# sofi_v7_main_rev2_1.net
KiCad netlist of a schematic drawn in EAGLE
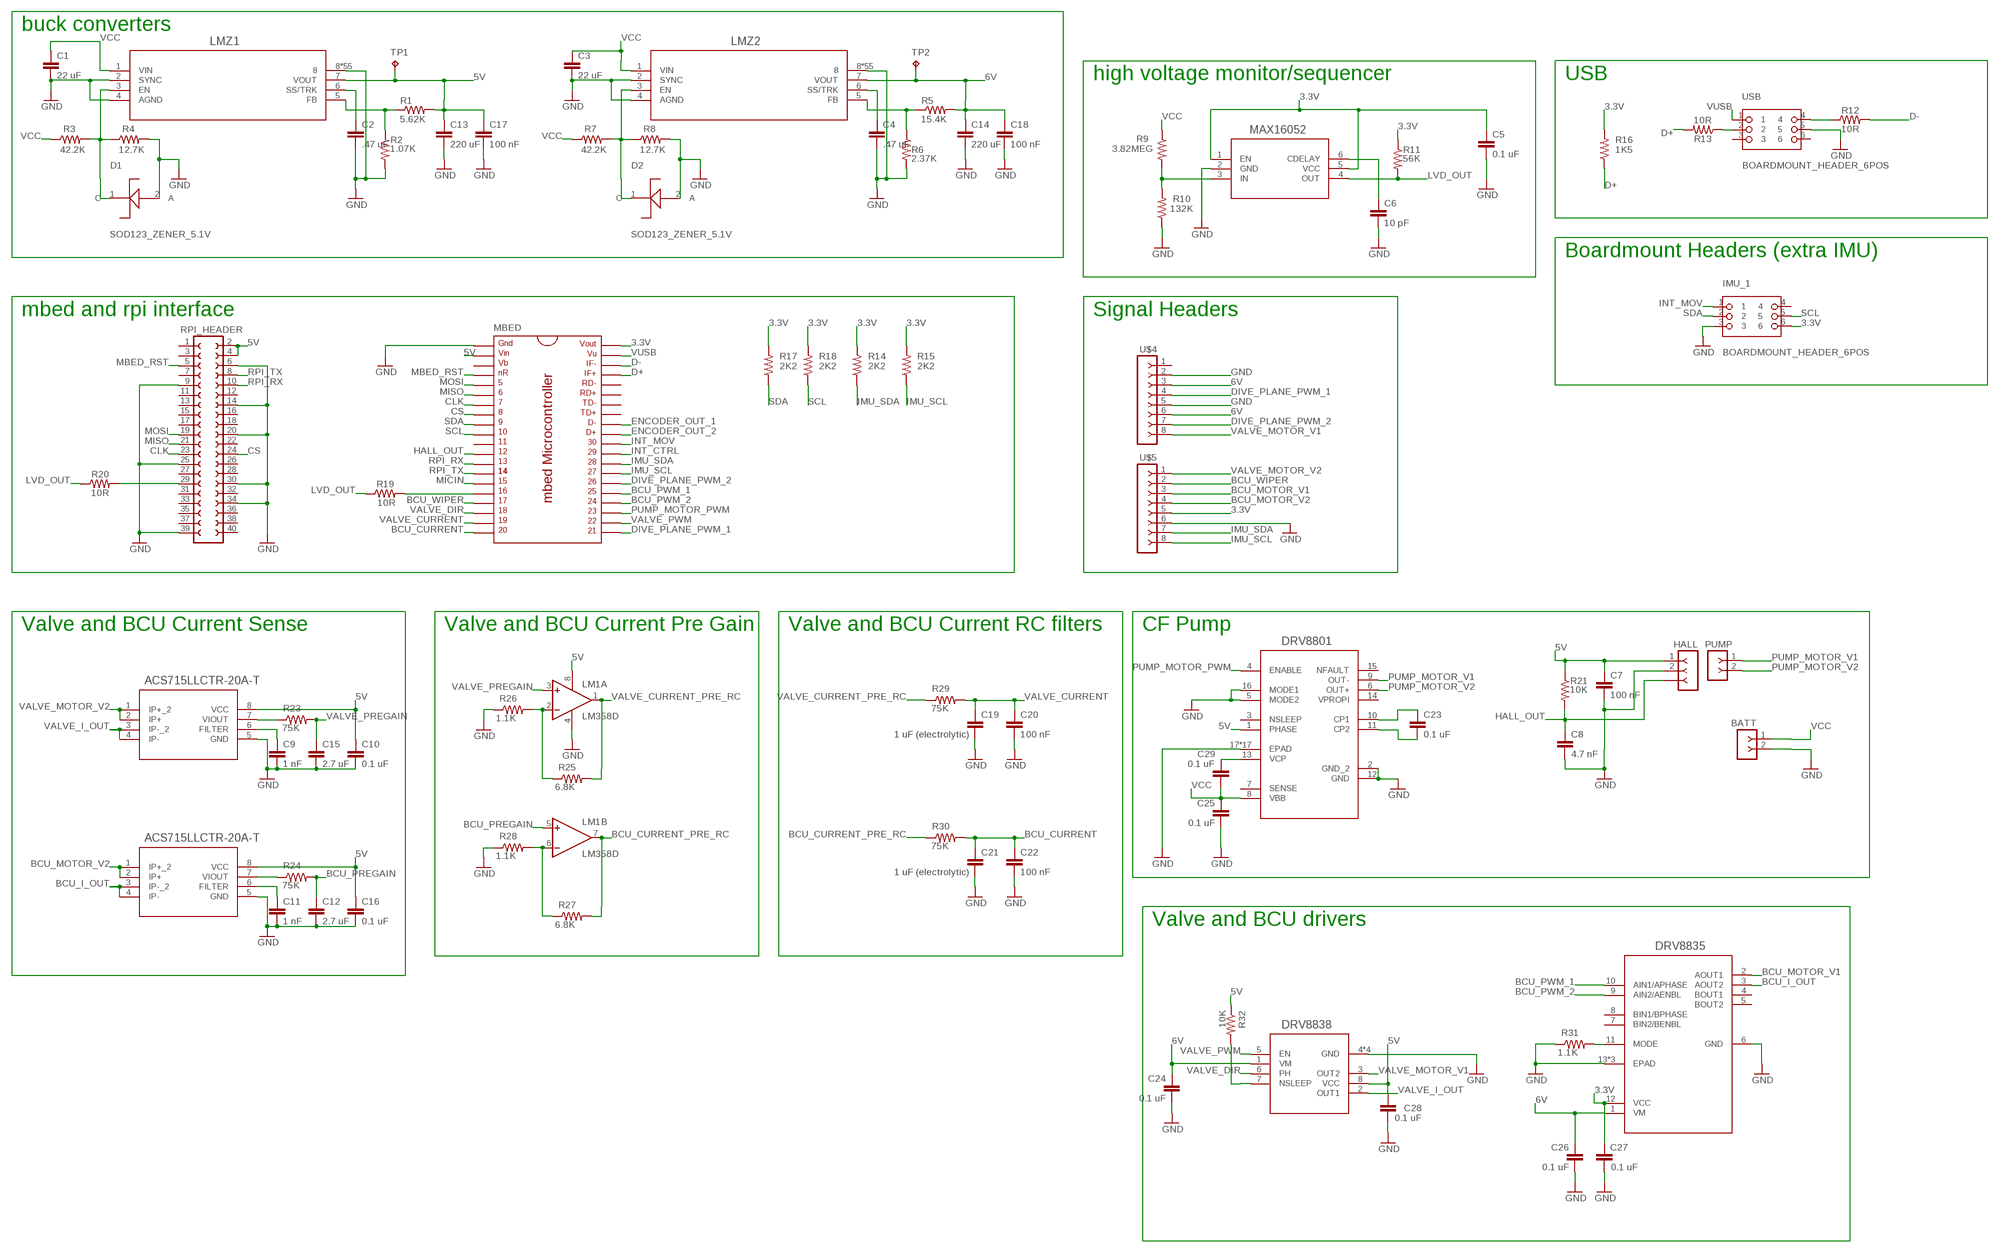
[diagram p0: schematic, sheet 1]

(export (version "E")
  (design (tool "Eeschema 10.0.6"))
  (components
    (comp (ref "BATT")
      (value "2POS_BLOCK")
      (footprint "eagle-import:2POS_BLOCK")
      (libsource (lib "eagle-import") (part "2POS_BLOCK"))
    )
    (comp (ref "C1")
      (value "22 uF")
      (footprint "eagle-import:C0805")
      (libsource (lib "eagle-import") (part "C-EUC0805"))
    )
    (comp (ref "C2")
      (value ".47 uF")
      (footprint "eagle-import:C0805")
      (libsource (lib "eagle-import") (part "C-EUC0805"))
    )
    (comp (ref "C3")
      (value "22 uF")
      (footprint "eagle-import:C0805")
      (libsource (lib "eagle-import") (part "C-EUC0805"))
    )
    (comp (ref "C4")
      (value ".47 uF")
      (footprint "eagle-import:C0805")
      (libsource (lib "eagle-import") (part "C-EUC0805"))
    )
    (comp (ref "C5")
      (value "0.1 uF")
      (footprint "eagle-import:C0805")
      (libsource (lib "eagle-import") (part "C-EUC0805"))
    )
    (comp (ref "C6")
      (value "10 pF")
      (footprint "eagle-import:C0603")
      (libsource (lib "eagle-import") (part "C-EUC0603"))
    )
    (comp (ref "C7")
      (value "100 nF")
      (footprint "eagle-import:C0805")
      (libsource (lib "eagle-import") (part "C-EUC0805"))
    )
    (comp (ref "C8")
      (value "4.7 nF")
      (footprint "eagle-import:C0805")
      (libsource (lib "eagle-import") (part "C-EUC0805"))
    )
    (comp (ref "C9")
      (value "1 nF")
      (footprint "eagle-import:C0603")
      (libsource (lib "eagle-import") (part "C-EUC0603"))
    )
    (comp (ref "C10")
      (value "0.1 uF")
      (footprint "eagle-import:C0603")
      (libsource (lib "eagle-import") (part "C-EUC0603"))
    )
    (comp (ref "C11")
      (value "1 nF")
      (footprint "eagle-import:C0603")
      (libsource (lib "eagle-import") (part "C-EUC0603"))
    )
    (comp (ref "C12")
      (value "2.7 uF")
      (footprint "eagle-import:C0603")
      (libsource (lib "eagle-import") (part "C-EUC0603"))
    )
    (comp (ref "C13")
      (value "220 uF")
      (footprint "eagle-import:C1206")
      (libsource (lib "eagle-import") (part "resistor_348_C-EUC1206"))
    )
    (comp (ref "C14")
      (value "220 uF")
      (footprint "eagle-import:C1206")
      (libsource (lib "eagle-import") (part "resistor_348_C-EUC1206"))
    )
    (comp (ref "C15")
      (value "2.7 uF")
      (footprint "eagle-import:C0603")
      (libsource (lib "eagle-import") (part "C-EUC0603"))
    )
    (comp (ref "C16")
      (value "0.1 uF")
      (footprint "eagle-import:C0603")
      (libsource (lib "eagle-import") (part "C-EUC0603"))
    )
    (comp (ref "C17")
      (value "100 nF")
      (footprint "eagle-import:C0805")
      (libsource (lib "eagle-import") (part "C-EUC0805"))
    )
    (comp (ref "C18")
      (value "100 nF")
      (footprint "eagle-import:C0805")
      (libsource (lib "eagle-import") (part "C-EUC0805"))
    )
    (comp (ref "C19")
      (value "1 uF (electrolytic)")
      (footprint "eagle-import:C0603")
      (libsource (lib "eagle-import") (part "C-EUC0603"))
    )
    (comp (ref "C20")
      (value "100 nF")
      (footprint "eagle-import:C0805")
      (libsource (lib "eagle-import") (part "C-EUC0805"))
    )
    (comp (ref "C21")
      (value "1 uF (electrolytic)")
      (footprint "eagle-import:C0603")
      (libsource (lib "eagle-import") (part "C-EUC0603"))
    )
    (comp (ref "C22")
      (value "100 nF")
      (footprint "eagle-import:C0805")
      (libsource (lib "eagle-import") (part "C-EUC0805"))
    )
    (comp (ref "C23")
      (value "0.1 uF")
      (footprint "eagle-import:C0805")
      (libsource (lib "eagle-import") (part "C-EUC0805"))
    )
    (comp (ref "C24")
      (value "0.1 uF")
      (footprint "eagle-import:C0603")
      (libsource (lib "eagle-import") (part "C-EUC0603"))
    )
    (comp (ref "C25")
      (value "0.1 uF")
      (footprint "eagle-import:C0603")
      (libsource (lib "eagle-import") (part "C-EUC0603"))
    )
    (comp (ref "C26")
      (value "0.1 uF")
      (footprint "eagle-import:C0603")
      (libsource (lib "eagle-import") (part "C-EUC0603"))
    )
    (comp (ref "C27")
      (value "0.1 uF")
      (footprint "eagle-import:C0603")
      (libsource (lib "eagle-import") (part "C-EUC0603"))
    )
    (comp (ref "C28")
      (value "0.1 uF")
      (footprint "eagle-import:C0603")
      (libsource (lib "eagle-import") (part "C-EUC0603"))
    )
    (comp (ref "C29")
      (value "0.1 uF")
      (footprint "eagle-import:C0805")
      (libsource (lib "eagle-import") (part "C-EUC0805"))
    )
    (comp (ref "D1")
      (value "SOD123_ZENER_5.1V")
      (footprint "eagle-import:SOD123_ZENER")
      (libsource (lib "eagle-import") (part "SOD123_ZENER_5.1V"))
    )
    (comp (ref "D2")
      (value "SOD123_ZENER_5.1V")
      (footprint "eagle-import:SOD123_ZENER")
      (libsource (lib "eagle-import") (part "SOD123_ZENER_5.1V"))
    )
    (comp (ref "DRV8801")
      (value "DRV8801RTYTRTY16-THERMAL")
      (footprint "eagle-import:RTY16-THERMAL")
      (libsource (lib "eagle-import") (part "DRV8801RTYTRTY16-THERMAL"))
    )
    (comp (ref "DRV8835")
      (value "DRV8835DSSRDSS12_P9X2_THERMAL")
      (footprint "eagle-import:DSS12_P9X2_THERMAL")
      (libsource (lib "eagle-import") (part "DRV8835DSSRDSS12_P9X2_THERMAL"))
    )
    (comp (ref "DRV8838")
      (value "DRV8838DSGTDSG8_P9X1P6_THERMAL")
      (footprint "eagle-import:DSG8_P9X1P6_THERMAL")
      (libsource (lib "eagle-import") (part "DRV8838DSGTDSG8_P9X1P6_THERMAL"))
    )
    (comp (ref "HALL")
      (value "3POS_TERMINAL")
      (footprint "eagle-import:3POS_TERMINAL")
      (libsource (lib "eagle-import") (part "3POS_TERMINAL"))
    )
    (comp (ref "IMU_1")
      (value "BOARDMOUNT_HEADER_6POS")
      (footprint "eagle-import:BOARDMOUNT_HEADER")
      (libsource (lib "eagle-import") (part "BOARDMOUNT_HEADER_6POS"))
    )
    (comp (ref "LM1")
      (value "LM358D")
      (footprint "eagle-import:SO08")
      (libsource (lib "eagle-import") (part "LM358D"))
    )
    (comp (ref "LMZ1")
      (value "LMZ23605TZE/NOPBTZA07A_THERMAL_TABBED")
      (footprint "eagle-import:TZA07A_THERMAL_TABBED")
      (libsource (lib "eagle-import") (part "LMZ23605TZE/NOPBTZA07A_THERMAL_TABBED"))
    )
    (comp (ref "LMZ2")
      (value "LMZ23605TZE/NOPBTZA07A_THERMAL_TABBED")
      (footprint "eagle-import:TZA07A_THERMAL_TABBED")
      (libsource (lib "eagle-import") (part "LMZ23605TZE/NOPBTZA07A_THERMAL_TABBED"))
    )
    (comp (ref "MAX16052")
      (value "MAX16052AUT+T")
      (footprint "eagle-import:21-0058I")
      (fields (field (name "MANUFACTURER_PART_NUMBER") "max16052aut+t"))
      (libsource (lib "eagle-import") (part "MAX16052AUT+T"))
    )
    (comp (ref "MBED")
      (value "MBED_MICROCONTROLLER")
      (footprint "eagle-import:DIL40_0.9")
      (libsource (lib "eagle-import") (part "MBED_MICROCONTROLLER"))
    )
    (comp (ref "PUMP")
      (value "2POS_BLOCK")
      (footprint "eagle-import:2POS_BLOCK")
      (libsource (lib "eagle-import") (part "2POS_BLOCK"))
    )
    (comp (ref "R1")
      (value "5.62K")
      (footprint "eagle-import:M0805")
      (libsource (lib "eagle-import") (part "R-US_M0805"))
    )
    (comp (ref "R2")
      (value "1.07K")
      (footprint "eagle-import:M0805")
      (libsource (lib "eagle-import") (part "R-US_M0805"))
    )
    (comp (ref "R3")
      (value "42.2K")
      (footprint "eagle-import:M0805")
      (libsource (lib "eagle-import") (part "R-US_M0805"))
    )
    (comp (ref "R4")
      (value "12.7K")
      (footprint "eagle-import:M0805")
      (libsource (lib "eagle-import") (part "R-US_M0805"))
    )
    (comp (ref "R5")
      (value "15.4K")
      (footprint "eagle-import:M0805")
      (libsource (lib "eagle-import") (part "R-US_M0805"))
    )
    (comp (ref "R6")
      (value "2.37K")
      (footprint "eagle-import:M0805")
      (libsource (lib "eagle-import") (part "R-US_M0805"))
    )
    (comp (ref "R7")
      (value "42.2K")
      (footprint "eagle-import:M0805")
      (libsource (lib "eagle-import") (part "R-US_M0805"))
    )
    (comp (ref "R8")
      (value "12.7K")
      (footprint "eagle-import:M0805")
      (libsource (lib "eagle-import") (part "R-US_M0805"))
    )
    (comp (ref "R9")
      (value "3.82MEG")
      (footprint "eagle-import:0603")
      (libsource (lib "eagle-import") (part "RESISTOR0603"))
    )
    (comp (ref "R10")
      (value "132K")
      (footprint "eagle-import:0603")
      (libsource (lib "eagle-import") (part "RESISTOR0603"))
    )
    (comp (ref "R11")
      (value "56K")
      (footprint "eagle-import:R0603")
      (libsource (lib "eagle-import") (part "R-US_R0603"))
    )
    (comp (ref "R12")
      (value "10R")
      (footprint "eagle-import:0603")
      (libsource (lib "eagle-import") (part "RESISTOR0603"))
    )
    (comp (ref "R13")
      (value "10R")
      (footprint "eagle-import:0603")
      (libsource (lib "eagle-import") (part "RESISTOR0603"))
    )
    (comp (ref "R14")
      (value "2K2")
      (footprint "eagle-import:0603")
      (libsource (lib "eagle-import") (part "RESISTOR0603"))
    )
    (comp (ref "R15")
      (value "2K2")
      (footprint "eagle-import:0603")
      (libsource (lib "eagle-import") (part "RESISTOR0603"))
    )
    (comp (ref "R16")
      (value "1K5")
      (footprint "eagle-import:0603")
      (libsource (lib "eagle-import") (part "RESISTOR0603"))
    )
    (comp (ref "R17")
      (value "2K2")
      (footprint "eagle-import:0603")
      (libsource (lib "eagle-import") (part "RESISTOR0603"))
    )
    (comp (ref "R18")
      (value "2K2")
      (footprint "eagle-import:0603")
      (libsource (lib "eagle-import") (part "RESISTOR0603"))
    )
    (comp (ref "R19")
      (value "10R")
      (footprint "eagle-import:0603")
      (libsource (lib "eagle-import") (part "RESISTOR0603"))
    )
    (comp (ref "R20")
      (value "10R")
      (footprint "eagle-import:0603")
      (libsource (lib "eagle-import") (part "RESISTOR0603"))
    )
    (comp (ref "R21")
      (value "10K")
      (footprint "eagle-import:M0805")
      (libsource (lib "eagle-import") (part "R-US_M0805"))
    )
    (comp (ref "R23")
      (value "75K")
      (footprint "eagle-import:M0805")
      (libsource (lib "eagle-import") (part "R-US_M0805"))
    )
    (comp (ref "R24")
      (value "75K")
      (footprint "eagle-import:M0805")
      (libsource (lib "eagle-import") (part "R-US_M0805"))
    )
    (comp (ref "R25")
      (value "6.8K")
      (footprint "eagle-import:M0805")
      (libsource (lib "eagle-import") (part "R-US_M0805"))
    )
    (comp (ref "R26")
      (value "1.1K")
      (footprint "eagle-import:M0805")
      (libsource (lib "eagle-import") (part "R-US_M0805"))
    )
    (comp (ref "R27")
      (value "6.8K")
      (footprint "eagle-import:M0805")
      (libsource (lib "eagle-import") (part "R-US_M0805"))
    )
    (comp (ref "R28")
      (value "1.1K")
      (footprint "eagle-import:M0805")
      (libsource (lib "eagle-import") (part "R-US_M0805"))
    )
    (comp (ref "R29")
      (value "75K")
      (footprint "eagle-import:M0805")
      (libsource (lib "eagle-import") (part "R-US_M0805"))
    )
    (comp (ref "R30")
      (value "75K")
      (footprint "eagle-import:M0805")
      (libsource (lib "eagle-import") (part "R-US_M0805"))
    )
    (comp (ref "R31")
      (value "1.1K")
      (footprint "eagle-import:M0805")
      (libsource (lib "eagle-import") (part "R-US_M0805"))
    )
    (comp (ref "R32")
      (value "10K")
      (footprint "eagle-import:M0805")
      (libsource (lib "eagle-import") (part "R-US_M0805"))
    )
    (comp (ref "RPI_HEADER")
      (value "FE20-2")
      (footprint "eagle-import:FE20-2")
      (libsource (lib "eagle-import") (part "FE20-2"))
    )
    (comp (ref "TP1")
      (value "TPB1,27")
      (footprint "eagle-import:B1,27")
      (libsource (lib "eagle-import") (part "TPB1,27"))
    )
    (comp (ref "TP2")
      (value "TPB1,27")
      (footprint "eagle-import:B1,27")
      (libsource (lib "eagle-import") (part "TPB1,27"))
    )
    (comp (ref "U$4")
      (value "8POS_TERMINAL")
      (footprint "eagle-import:8POS_TERMINAL")
      (libsource (lib "eagle-import") (part "8POS_TERMINAL"))
    )
    (comp (ref "U$5")
      (value "8POS_TERMINAL")
      (footprint "eagle-import:8POS_TERMINAL")
      (libsource (lib "eagle-import") (part "8POS_TERMINAL"))
    )
    (comp (ref "U3_BCU")
      (value "ACS715LLCTR-20A-T")
      (footprint "eagle-import:SOIC-8")
      (fields (field (name "MANUFACTURER_PART_NUMBER") "ACS715LLCTR20AT"))
      (libsource (lib "eagle-import") (part "ACS715LLCTR-20A-T"))
    )
    (comp (ref "U3_VALVE")
      (value "ACS715LLCTR-20A-T")
      (footprint "eagle-import:SOIC-8")
      (fields (field (name "MANUFACTURER_PART_NUMBER") "ACS715LLCTR20AT"))
      (libsource (lib "eagle-import") (part "ACS715LLCTR-20A-T"))
    )
    (comp (ref "USB")
      (value "BOARDMOUNT_HEADER_6POS")
      (footprint "eagle-import:BOARDMOUNT_HEADER")
      (libsource (lib "eagle-import") (part "BOARDMOUNT_HEADER_6POS"))
    )
  )
  (nets
    (net (code "1") (name "/3.3V") (class "Default")
      (node (ref "C27") (pin "1") (pinfunction "1_1") (pintype "passive"))
      (node (ref "C5") (pin "1") (pinfunction "1_1") (pintype "passive"))
      (node (ref "DRV8835") (pin "12") (pinfunction "VCC_12") (pintype "power_in"))
      (node (ref "IMU_1") (pin "6") (pinfunction "6_6") (pintype "bidirectional"))
      (node (ref "MAX16052") (pin "1") (pinfunction "EN_1") (pintype "input"))
      (node (ref "MAX16052") (pin "5") (pinfunction "VCC_5") (pintype "power_in"))
      (node (ref "MBED") (pin "40") (pinfunction "P$40_40") (pintype "bidirectional"))
      (node (ref "R11") (pin "1") (pinfunction "1_1") (pintype "passive"))
      (node (ref "R14") (pin "2") (pinfunction "2_2") (pintype "passive"))
      (node (ref "R15") (pin "2") (pinfunction "2_2") (pintype "passive"))
      (node (ref "R16") (pin "2") (pinfunction "2_2") (pintype "passive"))
      (node (ref "R17") (pin "2") (pinfunction "2_2") (pintype "passive"))
      (node (ref "R18") (pin "2") (pinfunction "2_2") (pintype "passive"))
      (node (ref "U$5") (pin "5") (pinfunction "5_5") (pintype "passive"))
    )
    (net (code "2") (name "/5V") (class "Default")
      (node (ref "C10") (pin "1") (pinfunction "1_1") (pintype "passive"))
      (node (ref "C13") (pin "1") (pinfunction "1_1") (pintype "passive"))
      (node (ref "C16") (pin "1") (pinfunction "1_1") (pintype "passive"))
      (node (ref "C17") (pin "1") (pinfunction "1_1") (pintype "passive"))
      (node (ref "C28") (pin "1") (pinfunction "1_1") (pintype "passive"))
      (node (ref "C7") (pin "1") (pinfunction "1_1") (pintype "passive"))
      (node (ref "DRV8801") (pin "1") (pinfunction "PHASE_1") (pintype "input"))
      (node (ref "DRV8838") (pin "8") (pinfunction "VCC_8") (pintype "power_in"))
      (node (ref "HALL") (pin "1") (pinfunction "1_1") (pintype "passive"))
      (node (ref "LM1") (pin "8") (pinfunction "V+_8") (pintype "power_in"))
      (node (ref "LMZ1") (pin "7") (pinfunction "VOUT_7") (pintype "output"))
      (node (ref "MBED") (pin "2") (pinfunction "P$2_2") (pintype "bidirectional"))
      (node (ref "R1") (pin "2") (pinfunction "2_2") (pintype "passive"))
      (node (ref "R21") (pin "1") (pinfunction "1_1") (pintype "passive"))
      (node (ref "R32") (pin "1") (pinfunction "1_1") (pintype "passive"))
      (node (ref "RPI_HEADER") (pin "2") (pinfunction "2_2") (pintype "passive"))
      (node (ref "RPI_HEADER") (pin "4") (pinfunction "4_4") (pintype "passive"))
      (node (ref "TP1") (pin "TP") (pinfunction "TP_TP") (pintype "input"))
      (node (ref "U3_BCU") (pin "8") (pinfunction "VCC_8") (pintype "power_in"))
      (node (ref "U3_VALVE") (pin "8") (pinfunction "VCC_8") (pintype "power_in"))
    )
    (net (code "3") (name "/6V") (class "Default")
      (node (ref "C14") (pin "1") (pinfunction "1_1") (pintype "passive"))
      (node (ref "C18") (pin "1") (pinfunction "1_1") (pintype "passive"))
      (node (ref "C24") (pin "1") (pinfunction "1_1") (pintype "passive"))
      (node (ref "C26") (pin "1") (pinfunction "1_1") (pintype "passive"))
      (node (ref "DRV8835") (pin "1") (pinfunction "VM_1") (pintype "power_in"))
      (node (ref "DRV8838") (pin "1") (pinfunction "VM_1") (pintype "power_in"))
      (node (ref "LMZ2") (pin "7") (pinfunction "VOUT_7") (pintype "output"))
      (node (ref "R5") (pin "2") (pinfunction "2_2") (pintype "passive"))
      (node (ref "TP2") (pin "TP") (pinfunction "TP_TP") (pintype "input"))
      (node (ref "U$4") (pin "3") (pinfunction "3_3") (pintype "passive"))
      (node (ref "U$4") (pin "6") (pinfunction "6_6") (pintype "passive"))
    )
    (net (code "4") (name "/BCU_CURRENT") (class "Default")
      (node (ref "C21") (pin "1") (pinfunction "1_1") (pintype "passive"))
      (node (ref "C22") (pin "1") (pinfunction "1_1") (pintype "passive"))
      (node (ref "MBED") (pin "20") (pinfunction "P$20_20") (pintype "bidirectional"))
      (node (ref "R30") (pin "2") (pinfunction "2_2") (pintype "passive"))
    )
    (net (code "5") (name "/BCU_CURRENT_PRE_RC") (class "Default")
      (node (ref "LM1") (pin "7") (pinfunction "OUT_7") (pintype "output"))
      (node (ref "R27") (pin "2") (pinfunction "2_2") (pintype "passive"))
      (node (ref "R30") (pin "1") (pinfunction "1_1") (pintype "passive"))
    )
    (net (code "6") (name "/BCU_I_OUT") (class "Default")
      (node (ref "DRV8835") (pin "3") (pinfunction "AOUT2_3") (pintype "output"))
      (node (ref "U3_BCU") (pin "3") (pinfunction "IP-_2_3") (pintype "output"))
      (node (ref "U3_BCU") (pin "4") (pinfunction "IP-_4") (pintype "output"))
    )
    (net (code "7") (name "/BCU_MOTOR_V1") (class "Default")
      (node (ref "DRV8835") (pin "2") (pinfunction "AOUT1_2") (pintype "output"))
      (node (ref "U$5") (pin "3") (pinfunction "3_3") (pintype "passive"))
    )
    (net (code "8") (name "/BCU_MOTOR_V2") (class "Default")
      (node (ref "U$5") (pin "4") (pinfunction "4_4") (pintype "passive"))
      (node (ref "U3_BCU") (pin "1") (pinfunction "IP+_2_1") (pintype "input"))
      (node (ref "U3_BCU") (pin "2") (pinfunction "IP+_2") (pintype "input"))
    )
    (net (code "9") (name "/BCU_PREGAIN") (class "Default")
      (node (ref "C12") (pin "1") (pinfunction "1_1") (pintype "passive"))
      (node (ref "LM1") (pin "5") (pinfunction "+IN_5") (pintype "input"))
      (node (ref "R24") (pin "2") (pinfunction "2_2") (pintype "passive"))
    )
    (net (code "10") (name "/BCU_PWM_1") (class "Default")
      (node (ref "DRV8835") (pin "10") (pinfunction "AIN1/APHASE_10") (pintype "input"))
      (node (ref "MBED") (pin "25") (pinfunction "P$25_25") (pintype "bidirectional"))
    )
    (net (code "11") (name "/BCU_PWM_2") (class "Default")
      (node (ref "DRV8835") (pin "9") (pinfunction "AIN2/AENBL_9") (pintype "input"))
      (node (ref "MBED") (pin "24") (pinfunction "P$24_24") (pintype "bidirectional"))
    )
    (net (code "12") (name "/BCU_WIPER") (class "Default")
      (node (ref "MBED") (pin "17") (pinfunction "P$17_17") (pintype "bidirectional"))
      (node (ref "U$5") (pin "2") (pinfunction "2_2") (pintype "passive"))
    )
    (net (code "13") (name "/CLK") (class "Default")
      (node (ref "MBED") (pin "7") (pinfunction "P$7_7") (pintype "bidirectional"))
      (node (ref "RPI_HEADER") (pin "23") (pinfunction "23_23") (pintype "passive"))
    )
    (net (code "14") (name "/CS") (class "Default")
      (node (ref "MBED") (pin "8") (pinfunction "P$8_8") (pintype "bidirectional"))
      (node (ref "RPI_HEADER") (pin "24") (pinfunction "24_24") (pintype "passive"))
    )
    (net (code "15") (name "/D+") (class "Default")
      (node (ref "MBED") (pin "37") (pinfunction "P$37_37") (pintype "bidirectional"))
      (node (ref "R13") (pin "2") (pinfunction "2_2") (pintype "passive"))
      (node (ref "R16") (pin "1") (pinfunction "1_1") (pintype "passive"))
    )
    (net (code "16") (name "/D-") (class "Default")
      (node (ref "MBED") (pin "38") (pinfunction "P$38_38") (pintype "bidirectional"))
      (node (ref "R12") (pin "2") (pinfunction "2_2") (pintype "passive"))
    )
    (net (code "17") (name "/DIVE_PLANE_PWM_1") (class "Default")
      (node (ref "MBED") (pin "21") (pinfunction "P$21_21") (pintype "bidirectional"))
      (node (ref "U$4") (pin "4") (pinfunction "4_4") (pintype "passive"))
    )
    (net (code "18") (name "/DIVE_PLANE_PWM_2") (class "Default")
      (node (ref "MBED") (pin "26") (pinfunction "P$26_26") (pintype "bidirectional"))
      (node (ref "U$4") (pin "7") (pinfunction "7_7") (pintype "passive"))
    )
    (net (code "19") (name "/ENCODER_OUT_1") (class "Default")
      (node (ref "MBED") (pin "32") (pinfunction "P$32_32") (pintype "bidirectional"))
    )
    (net (code "20") (name "/ENCODER_OUT_2") (class "Default")
      (node (ref "MBED") (pin "31") (pinfunction "P$31_31") (pintype "bidirectional"))
    )
    (net (code "21") (name "/HALL_OUT") (class "Default")
      (node (ref "C8") (pin "1") (pinfunction "1_1") (pintype "passive"))
      (node (ref "HALL") (pin "3") (pinfunction "3_3") (pintype "passive"))
      (node (ref "MBED") (pin "12") (pinfunction "P$12_12") (pintype "bidirectional"))
      (node (ref "R21") (pin "2") (pinfunction "2_2") (pintype "passive"))
    )
    (net (code "22") (name "/IMU_SCL") (class "Default")
      (node (ref "MBED") (pin "27") (pinfunction "P$27_27") (pintype "bidirectional"))
      (node (ref "R15") (pin "1") (pinfunction "1_1") (pintype "passive"))
      (node (ref "U$5") (pin "8") (pinfunction "8_8") (pintype "passive"))
    )
    (net (code "23") (name "/IMU_SDA") (class "Default")
      (node (ref "MBED") (pin "28") (pinfunction "P$28_28") (pintype "bidirectional"))
      (node (ref "R14") (pin "1") (pinfunction "1_1") (pintype "passive"))
      (node (ref "U$5") (pin "7") (pinfunction "7_7") (pintype "passive"))
    )
    (net (code "24") (name "/INT_CTRL") (class "Default")
      (node (ref "MBED") (pin "29") (pinfunction "P$29_29") (pintype "bidirectional"))
    )
    (net (code "25") (name "/INT_MOV") (class "Default")
      (node (ref "IMU_1") (pin "1") (pinfunction "1_1") (pintype "bidirectional"))
      (node (ref "MBED") (pin "30") (pinfunction "P$30_30") (pintype "bidirectional"))
    )
    (net (code "26") (name "/LVD_OUT") (class "Default")
      (node (ref "MAX16052") (pin "4") (pinfunction "OUT_4") (pintype "output"))
      (node (ref "R11") (pin "2") (pinfunction "2_2") (pintype "passive"))
      (node (ref "R19") (pin "1") (pinfunction "1_1") (pintype "passive"))
      (node (ref "R20") (pin "1") (pinfunction "1_1") (pintype "passive"))
    )
    (net (code "27") (name "/MBED_RST") (class "Default")
      (node (ref "MBED") (pin "4") (pinfunction "P$4_4") (pintype "bidirectional"))
      (node (ref "RPI_HEADER") (pin "5") (pinfunction "5_5") (pintype "passive"))
    )
    (net (code "28") (name "/MICIN") (class "Default")
      (node (ref "MBED") (pin "15") (pinfunction "P$15_15") (pintype "bidirectional"))
    )
    (net (code "29") (name "/MISO") (class "Default")
      (node (ref "MBED") (pin "6") (pinfunction "P$6_6") (pintype "bidirectional"))
      (node (ref "RPI_HEADER") (pin "21") (pinfunction "21_21") (pintype "passive"))
    )
    (net (code "30") (name "/MOSI") (class "Default")
      (node (ref "MBED") (pin "5") (pinfunction "P$5_5") (pintype "bidirectional"))
      (node (ref "RPI_HEADER") (pin "19") (pinfunction "19_19") (pintype "passive"))
    )
    (net (code "31") (name "/PUMP_MOTOR_PWM") (class "Default")
      (node (ref "DRV8801") (pin "4") (pinfunction "ENABLE_4") (pintype "input"))
      (node (ref "MBED") (pin "23") (pinfunction "P$23_23") (pintype "bidirectional"))
    )
    (net (code "32") (name "/PUMP_MOTOR_V1") (class "Default")
      (node (ref "DRV8801") (pin "9") (pinfunction "OUT-_9") (pintype "output"))
      (node (ref "PUMP") (pin "1") (pinfunction "1_1") (pintype "passive"))
    )
    (net (code "33") (name "/PUMP_MOTOR_V2") (class "Default")
      (node (ref "DRV8801") (pin "6") (pinfunction "OUT+_6") (pintype "output"))
      (node (ref "PUMP") (pin "2") (pinfunction "2_2") (pintype "passive"))
    )
    (net (code "34") (name "/RPI_RX") (class "Default")
      (node (ref "MBED") (pin "13") (pinfunction "P$13_13") (pintype "bidirectional"))
      (node (ref "RPI_HEADER") (pin "10") (pinfunction "10_10") (pintype "passive"))
    )
    (net (code "35") (name "/RPI_TX") (class "Default")
      (node (ref "MBED") (pin "14") (pinfunction "P$14_14") (pintype "bidirectional"))
      (node (ref "RPI_HEADER") (pin "8") (pinfunction "8_8") (pintype "passive"))
    )
    (net (code "36") (name "/SCL") (class "Default")
      (node (ref "IMU_1") (pin "5") (pinfunction "5_5") (pintype "bidirectional"))
      (node (ref "MBED") (pin "10") (pinfunction "P$10_10") (pintype "bidirectional"))
      (node (ref "R18") (pin "1") (pinfunction "1_1") (pintype "passive"))
    )
    (net (code "37") (name "/SDA") (class "Default")
      (node (ref "IMU_1") (pin "2") (pinfunction "2_2") (pintype "bidirectional"))
      (node (ref "MBED") (pin "9") (pinfunction "P$9_9") (pintype "bidirectional"))
      (node (ref "R17") (pin "1") (pinfunction "1_1") (pintype "passive"))
    )
    (net (code "38") (name "/SENSE") (class "Default")
      (node (ref "DRV8801") (pin "7") (pinfunction "SENSE_7") (pintype "power_in"))
    )
    (net (code "39") (name "/VALVE_CURRENT") (class "Default")
      (node (ref "C19") (pin "1") (pinfunction "1_1") (pintype "passive"))
      (node (ref "C20") (pin "1") (pinfunction "1_1") (pintype "passive"))
      (node (ref "MBED") (pin "19") (pinfunction "P$19_19") (pintype "bidirectional"))
      (node (ref "R29") (pin "2") (pinfunction "2_2") (pintype "passive"))
    )
    (net (code "40") (name "/VALVE_CURRENT_PRE_RC") (class "Default")
      (node (ref "LM1") (pin "1") (pinfunction "OUT_1") (pintype "output"))
      (node (ref "R25") (pin "2") (pinfunction "2_2") (pintype "passive"))
      (node (ref "R29") (pin "1") (pinfunction "1_1") (pintype "passive"))
    )
    (net (code "41") (name "/VALVE_DIR") (class "Default")
      (node (ref "DRV8838") (pin "6") (pinfunction "PH_6") (pintype "input"))
      (node (ref "MBED") (pin "18") (pinfunction "P$18_18") (pintype "bidirectional"))
    )
    (net (code "42") (name "/VALVE_I_OUT") (class "Default")
      (node (ref "DRV8838") (pin "2") (pinfunction "OUT1_2") (pintype "output"))
      (node (ref "U3_VALVE") (pin "3") (pinfunction "IP-_2_3") (pintype "output"))
      (node (ref "U3_VALVE") (pin "4") (pinfunction "IP-_4") (pintype "output"))
    )
    (net (code "43") (name "/VALVE_MOTOR_V1") (class "Default")
      (node (ref "DRV8838") (pin "3") (pinfunction "OUT2_3") (pintype "output"))
      (node (ref "U$4") (pin "8") (pinfunction "8_8") (pintype "passive"))
    )
    (net (code "44") (name "/VALVE_MOTOR_V2") (class "Default")
      (node (ref "U$5") (pin "1") (pinfunction "1_1") (pintype "passive"))
      (node (ref "U3_VALVE") (pin "1") (pinfunction "IP+_2_1") (pintype "input"))
      (node (ref "U3_VALVE") (pin "2") (pinfunction "IP+_2") (pintype "input"))
    )
    (net (code "45") (name "/VALVE_PREGAIN") (class "Default")
      (node (ref "C15") (pin "1") (pinfunction "1_1") (pintype "passive"))
      (node (ref "LM1") (pin "3") (pinfunction "+IN_3") (pintype "input"))
      (node (ref "R23") (pin "2") (pinfunction "2_2") (pintype "passive"))
    )
    (net (code "46") (name "/VALVE_PWM") (class "Default")
      (node (ref "DRV8838") (pin "5") (pinfunction "EN_5") (pintype "input"))
      (node (ref "MBED") (pin "22") (pinfunction "P$22_22") (pintype "bidirectional"))
    )
    (net (code "47") (name "/VCC") (class "Default")
      (node (ref "BATT") (pin "1") (pinfunction "1_1") (pintype "passive"))
      (node (ref "C1") (pin "1") (pinfunction "1_1") (pintype "passive"))
      (node (ref "C25") (pin "1") (pinfunction "1_1") (pintype "passive"))
      (node (ref "C29") (pin "2") (pinfunction "2_2") (pintype "passive"))
      (node (ref "C3") (pin "1") (pinfunction "1_1") (pintype "passive"))
      (node (ref "DRV8801") (pin "8") (pinfunction "VBB_8") (pintype "power_in"))
      (node (ref "LMZ1") (pin "1") (pinfunction "VIN_1") (pintype "input"))
      (node (ref "LMZ2") (pin "1") (pinfunction "VIN_1") (pintype "input"))
      (node (ref "R3") (pin "1") (pinfunction "1_1") (pintype "passive"))
      (node (ref "R7") (pin "1") (pinfunction "1_1") (pintype "passive"))
      (node (ref "R9") (pin "1") (pinfunction "1_1") (pintype "passive"))
    )
    (net (code "48") (name "/VUSB") (class "Default")
      (node (ref "MBED") (pin "39") (pinfunction "P$39_39") (pintype "bidirectional"))
      (node (ref "USB") (pin "1") (pinfunction "1_1") (pintype "bidirectional"))
    )
    (net (code "49") (name "GND") (class "Default")
      (node (ref "BATT") (pin "2") (pinfunction "2_2") (pintype "passive"))
      (node (ref "C1") (pin "2") (pinfunction "2_2") (pintype "passive"))
      (node (ref "C10") (pin "2") (pinfunction "2_2") (pintype "passive"))
      (node (ref "C11") (pin "2") (pinfunction "2_2") (pintype "passive"))
      (node (ref "C12") (pin "2") (pinfunction "2_2") (pintype "passive"))
      (node (ref "C13") (pin "2") (pinfunction "2_2") (pintype "passive"))
      (node (ref "C14") (pin "2") (pinfunction "2_2") (pintype "passive"))
      (node (ref "C15") (pin "2") (pinfunction "2_2") (pintype "passive"))
      (node (ref "C16") (pin "2") (pinfunction "2_2") (pintype "passive"))
      (node (ref "C17") (pin "2") (pinfunction "2_2") (pintype "passive"))
      (node (ref "C18") (pin "2") (pinfunction "2_2") (pintype "passive"))
      (node (ref "C19") (pin "2") (pinfunction "2_2") (pintype "passive"))
      (node (ref "C2") (pin "2") (pinfunction "2_2") (pintype "passive"))
      (node (ref "C20") (pin "2") (pinfunction "2_2") (pintype "passive"))
      (node (ref "C21") (pin "2") (pinfunction "2_2") (pintype "passive"))
      (node (ref "C22") (pin "2") (pinfunction "2_2") (pintype "passive"))
      (node (ref "C24") (pin "2") (pinfunction "2_2") (pintype "passive"))
      (node (ref "C25") (pin "2") (pinfunction "2_2") (pintype "passive"))
      (node (ref "C26") (pin "2") (pinfunction "2_2") (pintype "passive"))
      (node (ref "C27") (pin "2") (pinfunction "2_2") (pintype "passive"))
      (node (ref "C28") (pin "2") (pinfunction "2_2") (pintype "passive"))
      (node (ref "C3") (pin "2") (pinfunction "2_2") (pintype "passive"))
      (node (ref "C4") (pin "2") (pinfunction "2_2") (pintype "passive"))
      (node (ref "C5") (pin "2") (pinfunction "2_2") (pintype "passive"))
      (node (ref "C6") (pin "2") (pinfunction "2_2") (pintype "passive"))
      (node (ref "C7") (pin "2") (pinfunction "2_2") (pintype "passive"))
      (node (ref "C8") (pin "2") (pinfunction "2_2") (pintype "passive"))
      (node (ref "C9") (pin "2") (pinfunction "2_2") (pintype "passive"))
      (node (ref "D1") (pin "2") (pinfunction "A_2") (pintype "bidirectional"))
      (node (ref "D2") (pin "2") (pinfunction "A_2") (pintype "bidirectional"))
      (node (ref "DRV8801") (pin "12") (pinfunction "GND_12") (pintype "power_in"))
      (node (ref "DRV8801") (pin "16") (pinfunction "MODE1_16") (pintype "input"))
      (node (ref "DRV8801") (pin "17") (pinfunction "EPAD_17") (pintype "passive"))
      (node (ref "DRV8801") (pin "2") (pinfunction "GND_2_2") (pintype "power_in"))
      (node (ref "DRV8801") (pin "5") (pinfunction "MODE2_5") (pintype "input"))
      (node (ref "DRV8801") (pin "P$1") (pinfunction "EPAD_P$1") (pintype "passive"))
      (node (ref "DRV8801") (pin "P$10") (pinfunction "EPAD_P$10") (pintype "passive"))
      (node (ref "DRV8801") (pin "P$11") (pinfunction "EPAD_P$11") (pintype "passive"))
      (node (ref "DRV8801") (pin "P$12") (pinfunction "EPAD_P$12") (pintype "passive"))
      (node (ref "DRV8801") (pin "P$13") (pinfunction "EPAD_P$13") (pintype "passive"))
      (node (ref "DRV8801") (pin "P$14") (pinfunction "EPAD_P$14") (pintype "passive"))
      (node (ref "DRV8801") (pin "P$15") (pinfunction "EPAD_P$15") (pintype "passive"))
      (node (ref "DRV8801") (pin "P$16") (pinfunction "EPAD_P$16") (pintype "passive"))
      (node (ref "DRV8801") (pin "P$2") (pinfunction "EPAD_P$2") (pintype "passive"))
      (node (ref "DRV8801") (pin "P$3") (pinfunction "EPAD_P$3") (pintype "passive"))
      (node (ref "DRV8801") (pin "P$4") (pinfunction "EPAD_P$4") (pintype "passive"))
      (node (ref "DRV8801") (pin "P$5") (pinfunction "EPAD_P$5") (pintype "passive"))
      (node (ref "DRV8801") (pin "P$6") (pinfunction "EPAD_P$6") (pintype "passive"))
      (node (ref "DRV8801") (pin "P$7") (pinfunction "EPAD_P$7") (pintype "passive"))
      (node (ref "DRV8801") (pin "P$8") (pinfunction "EPAD_P$8") (pintype "passive"))
      (node (ref "DRV8801") (pin "P$9") (pinfunction "EPAD_P$9") (pintype "passive"))
      (node (ref "DRV8835") (pin "13") (pinfunction "EPAD_13") (pintype "passive"))
      (node (ref "DRV8835") (pin "6") (pinfunction "GND_6") (pintype "power_in"))
      (node (ref "DRV8835") (pin "P$1") (pinfunction "EPAD_P$1") (pintype "passive"))
      (node (ref "DRV8835") (pin "P$2") (pinfunction "EPAD_P$2") (pintype "passive"))
      (node (ref "DRV8838") (pin "4") (pinfunction "GND_4") (pintype "power_in"))
      (node (ref "DRV8838") (pin "9") (pinfunction "GND_9") (pintype "power_in"))
      (node (ref "DRV8838") (pin "P$1") (pinfunction "GND_P$1") (pintype "power_in"))
      (node (ref "DRV8838") (pin "P$2") (pinfunction "GND_P$2") (pintype "power_in"))
      (node (ref "HALL") (pin "2") (pinfunction "2_2") (pintype "passive"))
      (node (ref "IMU_1") (pin "3") (pinfunction "3_3") (pintype "bidirectional"))
      (node (ref "LM1") (pin "4") (pinfunction "V-_4") (pintype "power_in"))
      (node (ref "LMZ1") (pin "2") (pinfunction "SYNC_2") (pintype "input"))
      (node (ref "LMZ1") (pin "4") (pinfunction "AGND_4") (pintype "power_in"))
      (node (ref "LMZ1") (pin "8") (pinfunction "8_8") (pintype "passive"))
      (node (ref "LMZ1") (pin "P$1") (pinfunction "8_P$1") (pintype "passive"))
      (node (ref "LMZ1") (pin "P$10") (pinfunction "8_P$10") (pintype "passive"))
      (node (ref "LMZ1") (pin "P$11") (pinfunction "8_P$11") (pintype "passive"))
      (node (ref "LMZ1") (pin "P$12") (pinfunction "8_P$12") (pintype "passive"))
      (node (ref "LMZ1") (pin "P$13") (pinfunction "8_P$13") (pintype "passive"))
      (node (ref "LMZ1") (pin "P$14") (pinfunction "8_P$14") (pintype "passive"))
      (node (ref "LMZ1") (pin "P$15") (pinfunction "8_P$15") (pintype "passive"))
      (node (ref "LMZ1") (pin "P$16") (pinfunction "8_P$16") (pintype "passive"))
      (node (ref "LMZ1") (pin "P$17") (pinfunction "8_P$17") (pintype "passive"))
      (node (ref "LMZ1") (pin "P$18") (pinfunction "8_P$18") (pintype "passive"))
      (node (ref "LMZ1") (pin "P$19") (pinfunction "8_P$19") (pintype "passive"))
      (node (ref "LMZ1") (pin "P$2") (pinfunction "8_P$2") (pintype "passive"))
      (node (ref "LMZ1") (pin "P$20") (pinfunction "8_P$20") (pintype "passive"))
      (node (ref "LMZ1") (pin "P$21") (pinfunction "8_P$21") (pintype "passive"))
      (node (ref "LMZ1") (pin "P$22") (pinfunction "8_P$22") (pintype "passive"))
      (node (ref "LMZ1") (pin "P$23") (pinfunction "8_P$23") (pintype "passive"))
      (node (ref "LMZ1") (pin "P$24") (pinfunction "8_P$24") (pintype "passive"))
      (node (ref "LMZ1") (pin "P$25") (pinfunction "8_P$25") (pintype "passive"))
      (node (ref "LMZ1") (pin "P$26") (pinfunction "8_P$26") (pintype "passive"))
      (node (ref "LMZ1") (pin "P$27") (pinfunction "8_P$27") (pintype "passive"))
      (node (ref "LMZ1") (pin "P$28") (pinfunction "8_P$28") (pintype "passive"))
      (node (ref "LMZ1") (pin "P$29") (pinfunction "8_P$29") (pintype "passive"))
      (node (ref "LMZ1") (pin "P$3") (pinfunction "8_P$3") (pintype "passive"))
      (node (ref "LMZ1") (pin "P$30") (pinfunction "8_P$30") (pintype "passive"))
      (node (ref "LMZ1") (pin "P$31") (pinfunction "8_P$31") (pintype "passive"))
      (node (ref "LMZ1") (pin "P$32") (pinfunction "8_P$32") (pintype "passive"))
      (node (ref "LMZ1") (pin "P$33") (pinfunction "8_P$33") (pintype "passive"))
      (node (ref "LMZ1") (pin "P$34") (pinfunction "8_P$34") (pintype "passive"))
      (node (ref "LMZ1") (pin "P$35") (pinfunction "8_P$35") (pintype "passive"))
      (node (ref "LMZ1") (pin "P$36") (pinfunction "8_P$36") (pintype "passive"))
      (node (ref "LMZ1") (pin "P$37") (pinfunction "8_P$37") (pintype "passive"))
      (node (ref "LMZ1") (pin "P$38") (pinfunction "8_P$38") (pintype "passive"))
      (node (ref "LMZ1") (pin "P$39") (pinfunction "8_P$39") (pintype "passive"))
      (node (ref "LMZ1") (pin "P$4") (pinfunction "8_P$4") (pintype "passive"))
      (node (ref "LMZ1") (pin "P$40") (pinfunction "8_P$40") (pintype "passive"))
      (node (ref "LMZ1") (pin "P$41") (pinfunction "8_P$41") (pintype "passive"))
      (node (ref "LMZ1") (pin "P$42") (pinfunction "8_P$42") (pintype "passive"))
      (node (ref "LMZ1") (pin "P$43") (pinfunction "8_P$43") (pintype "passive"))
      (node (ref "LMZ1") (pin "P$44") (pinfunction "8_P$44") (pintype "passive"))
      (node (ref "LMZ1") (pin "P$45") (pinfunction "8_P$45") (pintype "passive"))
      (node (ref "LMZ1") (pin "P$46") (pinfunction "8_P$46") (pintype "passive"))
      (node (ref "LMZ1") (pin "P$47") (pinfunction "8_P$47") (pintype "passive"))
      (node (ref "LMZ1") (pin "P$48") (pinfunction "8_P$48") (pintype "passive"))
      (node (ref "LMZ1") (pin "P$49") (pinfunction "8_P$49") (pintype "passive"))
      (node (ref "LMZ1") (pin "P$5") (pinfunction "8_P$5") (pintype "passive"))
      (node (ref "LMZ1") (pin "P$50") (pinfunction "8_P$50") (pintype "passive"))
      (node (ref "LMZ1") (pin "P$51") (pinfunction "8_P$51") (pintype "passive"))
      (node (ref "LMZ1") (pin "P$52") (pinfunction "8_P$52") (pintype "passive"))
      (node (ref "LMZ1") (pin "P$53") (pinfunction "8_P$53") (pintype "passive"))
      (node (ref "LMZ1") (pin "P$54") (pinfunction "8_P$54") (pintype "passive"))
      (node (ref "LMZ1") (pin "P$6") (pinfunction "8_P$6") (pintype "passive"))
      (node (ref "LMZ1") (pin "P$7") (pinfunction "8_P$7") (pintype "passive"))
      (node (ref "LMZ1") (pin "P$8") (pinfunction "8_P$8") (pintype "passive"))
      (node (ref "LMZ1") (pin "P$9") (pinfunction "8_P$9") (pintype "passive"))
      (node (ref "LMZ2") (pin "2") (pinfunction "SYNC_2") (pintype "input"))
      (node (ref "LMZ2") (pin "4") (pinfunction "AGND_4") (pintype "power_in"))
      (node (ref "LMZ2") (pin "8") (pinfunction "8_8") (pintype "passive"))
      (node (ref "LMZ2") (pin "P$1") (pinfunction "8_P$1") (pintype "passive"))
      (node (ref "LMZ2") (pin "P$10") (pinfunction "8_P$10") (pintype "passive"))
      (node (ref "LMZ2") (pin "P$11") (pinfunction "8_P$11") (pintype "passive"))
      (node (ref "LMZ2") (pin "P$12") (pinfunction "8_P$12") (pintype "passive"))
      (node (ref "LMZ2") (pin "P$13") (pinfunction "8_P$13") (pintype "passive"))
      (node (ref "LMZ2") (pin "P$14") (pinfunction "8_P$14") (pintype "passive"))
      (node (ref "LMZ2") (pin "P$15") (pinfunction "8_P$15") (pintype "passive"))
      (node (ref "LMZ2") (pin "P$16") (pinfunction "8_P$16") (pintype "passive"))
      (node (ref "LMZ2") (pin "P$17") (pinfunction "8_P$17") (pintype "passive"))
      (node (ref "LMZ2") (pin "P$18") (pinfunction "8_P$18") (pintype "passive"))
      (node (ref "LMZ2") (pin "P$19") (pinfunction "8_P$19") (pintype "passive"))
      (node (ref "LMZ2") (pin "P$2") (pinfunction "8_P$2") (pintype "passive"))
      (node (ref "LMZ2") (pin "P$20") (pinfunction "8_P$20") (pintype "passive"))
      (node (ref "LMZ2") (pin "P$21") (pinfunction "8_P$21") (pintype "passive"))
      (node (ref "LMZ2") (pin "P$22") (pinfunction "8_P$22") (pintype "passive"))
      (node (ref "LMZ2") (pin "P$23") (pinfunction "8_P$23") (pintype "passive"))
      (node (ref "LMZ2") (pin "P$24") (pinfunction "8_P$24") (pintype "passive"))
      (node (ref "LMZ2") (pin "P$25") (pinfunction "8_P$25") (pintype "passive"))
      (node (ref "LMZ2") (pin "P$26") (pinfunction "8_P$26") (pintype "passive"))
      (node (ref "LMZ2") (pin "P$27") (pinfunction "8_P$27") (pintype "passive"))
      (node (ref "LMZ2") (pin "P$28") (pinfunction "8_P$28") (pintype "passive"))
      (node (ref "LMZ2") (pin "P$29") (pinfunction "8_P$29") (pintype "passive"))
      (node (ref "LMZ2") (pin "P$3") (pinfunction "8_P$3") (pintype "passive"))
      (node (ref "LMZ2") (pin "P$30") (pinfunction "8_P$30") (pintype "passive"))
      (node (ref "LMZ2") (pin "P$31") (pinfunction "8_P$31") (pintype "passive"))
      (node (ref "LMZ2") (pin "P$32") (pinfunction "8_P$32") (pintype "passive"))
      (node (ref "LMZ2") (pin "P$33") (pinfunction "8_P$33") (pintype "passive"))
      (node (ref "LMZ2") (pin "P$34") (pinfunction "8_P$34") (pintype "passive"))
      (node (ref "LMZ2") (pin "P$35") (pinfunction "8_P$35") (pintype "passive"))
      (node (ref "LMZ2") (pin "P$36") (pinfunction "8_P$36") (pintype "passive"))
      (node (ref "LMZ2") (pin "P$37") (pinfunction "8_P$37") (pintype "passive"))
      (node (ref "LMZ2") (pin "P$38") (pinfunction "8_P$38") (pintype "passive"))
      (node (ref "LMZ2") (pin "P$39") (pinfunction "8_P$39") (pintype "passive"))
      (node (ref "LMZ2") (pin "P$4") (pinfunction "8_P$4") (pintype "passive"))
      (node (ref "LMZ2") (pin "P$40") (pinfunction "8_P$40") (pintype "passive"))
      (node (ref "LMZ2") (pin "P$41") (pinfunction "8_P$41") (pintype "passive"))
      (node (ref "LMZ2") (pin "P$42") (pinfunction "8_P$42") (pintype "passive"))
      (node (ref "LMZ2") (pin "P$43") (pinfunction "8_P$43") (pintype "passive"))
      (node (ref "LMZ2") (pin "P$44") (pinfunction "8_P$44") (pintype "passive"))
      (node (ref "LMZ2") (pin "P$45") (pinfunction "8_P$45") (pintype "passive"))
      (node (ref "LMZ2") (pin "P$46") (pinfunction "8_P$46") (pintype "passive"))
      (node (ref "LMZ2") (pin "P$47") (pinfunction "8_P$47") (pintype "passive"))
      (node (ref "LMZ2") (pin "P$48") (pinfunction "8_P$48") (pintype "passive"))
      (node (ref "LMZ2") (pin "P$49") (pinfunction "8_P$49") (pintype "passive"))
      (node (ref "LMZ2") (pin "P$5") (pinfunction "8_P$5") (pintype "passive"))
      (node (ref "LMZ2") (pin "P$50") (pinfunction "8_P$50") (pintype "passive"))
      (node (ref "LMZ2") (pin "P$51") (pinfunction "8_P$51") (pintype "passive"))
      (node (ref "LMZ2") (pin "P$52") (pinfunction "8_P$52") (pintype "passive"))
      (node (ref "LMZ2") (pin "P$53") (pinfunction "8_P$53") (pintype "passive"))
      (node (ref "LMZ2") (pin "P$54") (pinfunction "8_P$54") (pintype "passive"))
      (node (ref "LMZ2") (pin "P$6") (pinfunction "8_P$6") (pintype "passive"))
      (node (ref "LMZ2") (pin "P$7") (pinfunction "8_P$7") (pintype "passive"))
      (node (ref "LMZ2") (pin "P$8") (pinfunction "8_P$8") (pintype "passive"))
      (node (ref "LMZ2") (pin "P$9") (pinfunction "8_P$9") (pintype "passive"))
      (node (ref "MAX16052") (pin "2") (pinfunction "GND_2") (pintype "power_in"))
      (node (ref "MBED") (pin "1") (pinfunction "P$1_1") (pintype "bidirectional"))
      (node (ref "R10") (pin "1") (pinfunction "1_1") (pintype "passive"))
      (node (ref "R2") (pin "2") (pinfunction "2_2") (pintype "passive"))
      (node (ref "R26") (pin "1") (pinfunction "1_1") (pintype "passive"))
      (node (ref "R28") (pin "1") (pinfunction "1_1") (pintype "passive"))
      (node (ref "R31") (pin "1") (pinfunction "1_1") (pintype "passive"))
      (node (ref "R4") (pin "2") (pinfunction "2_2") (pintype "passive"))
      (node (ref "R6") (pin "2") (pinfunction "2_2") (pintype "passive"))
      (node (ref "R8") (pin "2") (pinfunction "2_2") (pintype "passive"))
      (node (ref "RPI_HEADER") (pin "14") (pinfunction "14_14") (pintype "passive"))
      (node (ref "RPI_HEADER") (pin "20") (pinfunction "20_20") (pintype "passive"))
      (node (ref "RPI_HEADER") (pin "25") (pinfunction "25_25") (pintype "passive"))
      (node (ref "RPI_HEADER") (pin "30") (pinfunction "30_30") (pintype "passive"))
      (node (ref "RPI_HEADER") (pin "34") (pinfunction "34_34") (pintype "passive"))
      (node (ref "RPI_HEADER") (pin "39") (pinfunction "39_39") (pintype "passive"))
      (node (ref "RPI_HEADER") (pin "6") (pinfunction "6_6") (pintype "passive"))
      (node (ref "RPI_HEADER") (pin "9") (pinfunction "9_9") (pintype "passive"))
      (node (ref "U$4") (pin "2") (pinfunction "2_2") (pintype "passive"))
      (node (ref "U$4") (pin "5") (pinfunction "5_5") (pintype "passive"))
      (node (ref "U$5") (pin "6") (pinfunction "6_6") (pintype "passive"))
      (node (ref "U3_BCU") (pin "5") (pinfunction "GND_5") (pintype "power_in"))
      (node (ref "U3_VALVE") (pin "5") (pinfunction "GND_5") (pintype "power_in"))
      (node (ref "USB") (pin "5") (pinfunction "5_5") (pintype "bidirectional"))
    )
    (net (code "50") (name "Net-(D1-C)") (class "Default")
      (node (ref "D1") (pin "1") (pinfunction "C_1") (pintype "bidirectional"))
      (node (ref "LMZ1") (pin "3") (pinfunction "EN_3") (pintype "input"))
      (node (ref "R3") (pin "2") (pinfunction "2_2") (pintype "passive"))
      (node (ref "R4") (pin "1") (pinfunction "1_1") (pintype "passive"))
    )
    (net (code "51") (name "Net-(D2-C)") (class "Default")
      (node (ref "D2") (pin "1") (pinfunction "C_1") (pintype "bidirectional"))
      (node (ref "LMZ2") (pin "3") (pinfunction "EN_3") (pintype "input"))
      (node (ref "R7") (pin "2") (pinfunction "2_2") (pintype "passive"))
      (node (ref "R8") (pin "1") (pinfunction "1_1") (pintype "passive"))
    )
    (net (code "52") (name "Net-(DRV8801-CP1)") (class "Default")
      (node (ref "C23") (pin "1") (pinfunction "1_1") (pintype "passive"))
      (node (ref "DRV8801") (pin "10") (pinfunction "CP1_10") (pintype "passive"))
    )
    (net (code "53") (name "Net-(DRV8801-CP2)") (class "Default")
      (node (ref "C23") (pin "2") (pinfunction "2_2") (pintype "passive"))
      (node (ref "DRV8801") (pin "11") (pinfunction "CP2_11") (pintype "passive"))
    )
    (net (code "54") (name "Net-(DRV8801-VCP)") (class "Default")
      (node (ref "C29") (pin "1") (pinfunction "1_1") (pintype "passive"))
      (node (ref "DRV8801") (pin "13") (pinfunction "VCP_13") (pintype "passive"))
    )
    (net (code "55") (name "Net-(DRV8835-MODE)") (class "Default")
      (node (ref "DRV8835") (pin "11") (pinfunction "MODE_11") (pintype "input"))
      (node (ref "R31") (pin "2") (pinfunction "2_2") (pintype "passive"))
    )
    (net (code "56") (name "Net-(DRV8838-NSLEEP)") (class "Default")
      (node (ref "DRV8838") (pin "7") (pinfunction "NSLEEP_7") (pintype "input"))
      (node (ref "R32") (pin "2") (pinfunction "2_2") (pintype "passive"))
    )
    (net (code "57") (name "Net-(LM1A--IN)") (class "Default")
      (node (ref "LM1") (pin "2") (pinfunction "-IN_2") (pintype "input"))
      (node (ref "R25") (pin "1") (pinfunction "1_1") (pintype "passive"))
      (node (ref "R26") (pin "2") (pinfunction "2_2") (pintype "passive"))
    )
    (net (code "58") (name "Net-(LM1B--IN)") (class "Default")
      (node (ref "LM1") (pin "6") (pinfunction "-IN_6") (pintype "input"))
      (node (ref "R27") (pin "1") (pinfunction "1_1") (pintype "passive"))
      (node (ref "R28") (pin "2") (pinfunction "2_2") (pintype "passive"))
    )
    (net (code "59") (name "Net-(LMZ1-FB)") (class "Default")
      (node (ref "LMZ1") (pin "5") (pinfunction "FB_5") (pintype "input"))
      (node (ref "R1") (pin "1") (pinfunction "1_1") (pintype "passive"))
      (node (ref "R2") (pin "1") (pinfunction "1_1") (pintype "passive"))
    )
    (net (code "60") (name "Net-(LMZ1-SS{slash}TRK)") (class "Default")
      (node (ref "C2") (pin "1") (pinfunction "1_1") (pintype "passive"))
      (node (ref "LMZ1") (pin "6") (pinfunction "SS/TRK_6") (pintype "bidirectional"))
    )
    (net (code "61") (name "Net-(LMZ2-FB)") (class "Default")
      (node (ref "LMZ2") (pin "5") (pinfunction "FB_5") (pintype "input"))
      (node (ref "R5") (pin "1") (pinfunction "1_1") (pintype "passive"))
      (node (ref "R6") (pin "1") (pinfunction "1_1") (pintype "passive"))
    )
    (net (code "62") (name "Net-(LMZ2-SS{slash}TRK)") (class "Default")
      (node (ref "C4") (pin "1") (pinfunction "1_1") (pintype "passive"))
      (node (ref "LMZ2") (pin "6") (pinfunction "SS/TRK_6") (pintype "bidirectional"))
    )
    (net (code "63") (name "Net-(MAX16052-CDELAY)") (class "Default")
      (node (ref "C6") (pin "1") (pinfunction "1_1") (pintype "passive"))
      (node (ref "MAX16052") (pin "6") (pinfunction "CDELAY_6") (pintype "input"))
    )
    (net (code "64") (name "Net-(MAX16052-IN)") (class "Default")
      (node (ref "MAX16052") (pin "3") (pinfunction "IN_3") (pintype "input"))
      (node (ref "R10") (pin "2") (pinfunction "2_2") (pintype "passive"))
      (node (ref "R9") (pin "2") (pinfunction "2_2") (pintype "passive"))
    )
    (net (code "65") (name "Net-(MBED-P$16)") (class "Default")
      (node (ref "MBED") (pin "16") (pinfunction "P$16_16") (pintype "bidirectional"))
      (node (ref "R19") (pin "2") (pinfunction "2_2") (pintype "passive"))
    )
    (net (code "66") (name "Net-(R12-Pad1)") (class "Default")
      (node (ref "R12") (pin "1") (pinfunction "1_1") (pintype "passive"))
      (node (ref "USB") (pin "4") (pinfunction "4_4") (pintype "bidirectional"))
    )
    (net (code "67") (name "Net-(R13-Pad1)") (class "Default")
      (node (ref "R13") (pin "1") (pinfunction "1_1") (pintype "passive"))
      (node (ref "USB") (pin "2") (pinfunction "2_2") (pintype "bidirectional"))
    )
    (net (code "68") (name "Net-(R20-Pad2)") (class "Default")
      (node (ref "R20") (pin "2") (pinfunction "2_2") (pintype "passive"))
      (node (ref "RPI_HEADER") (pin "29") (pinfunction "29_29") (pintype "passive"))
    )
    (net (code "69") (name "Net-(U3_BCU-FILTER)") (class "Default")
      (node (ref "C11") (pin "1") (pinfunction "1_1") (pintype "passive"))
      (node (ref "U3_BCU") (pin "6") (pinfunction "FILTER_6") (pintype "passive"))
    )
    (net (code "70") (name "Net-(U3_BCU-VIOUT)") (class "Default")
      (node (ref "R24") (pin "1") (pinfunction "1_1") (pintype "passive"))
      (node (ref "U3_BCU") (pin "7") (pinfunction "VIOUT_7") (pintype "output"))
    )
    (net (code "71") (name "Net-(U3_VALVE-FILTER)") (class "Default")
      (node (ref "C9") (pin "1") (pinfunction "1_1") (pintype "passive"))
      (node (ref "U3_VALVE") (pin "6") (pinfunction "FILTER_6") (pintype "passive"))
    )
    (net (code "72") (name "Net-(U3_VALVE-VIOUT)") (class "Default")
      (node (ref "R23") (pin "1") (pinfunction "1_1") (pintype "passive"))
      (node (ref "U3_VALVE") (pin "7") (pinfunction "VIOUT_7") (pintype "output"))
    )
    (net (code "73") (name "unconnected-(DRV8801-NFAULT-Pad15)") (class "Default")
      (node (ref "DRV8801") (pin "15") (pinfunction "NFAULT_15") (pintype "output"))
    )
    (net (code "74") (name "unconnected-(DRV8801-NSLEEP-Pad3)") (class "Default")
      (node (ref "DRV8801") (pin "3") (pinfunction "NSLEEP_3") (pintype "input"))
    )
    (net (code "75") (name "unconnected-(DRV8801-VPROPI-Pad14)") (class "Default")
      (node (ref "DRV8801") (pin "14") (pinfunction "VPROPI_14") (pintype "output"))
    )
    (net (code "76") (name "unconnected-(DRV8835-BIN1{slash}BPHASE-Pad8)") (class "Default")
      (node (ref "DRV8835") (pin "8") (pinfunction "BIN1/BPHASE_8") (pintype "input"))
    )
    (net (code "77") (name "unconnected-(DRV8835-BIN2{slash}BENBL-Pad7)") (class "Default")
      (node (ref "DRV8835") (pin "7") (pinfunction "BIN2/BENBL_7") (pintype "input"))
    )
    (net (code "78") (name "unconnected-(DRV8835-BOUT1-Pad4)") (class "Default")
      (node (ref "DRV8835") (pin "4") (pinfunction "BOUT1_4") (pintype "output"))
    )
    (net (code "79") (name "unconnected-(DRV8835-BOUT2-Pad5)") (class "Default")
      (node (ref "DRV8835") (pin "5") (pinfunction "BOUT2_5") (pintype "output"))
    )
    (net (code "80") (name "unconnected-(IMU_1-Pad4)") (class "Default")
      (node (ref "IMU_1") (pin "4") (pinfunction "4_4") (pintype "bidirectional"))
    )
    (net (code "81") (name "unconnected-(MBED-P$3-Pad3)") (class "Default")
      (node (ref "MBED") (pin "3") (pinfunction "P$3_3") (pintype "bidirectional"))
    )
    (net (code "82") (name "unconnected-(MBED-P$11-Pad11)") (class "Default")
      (node (ref "MBED") (pin "11") (pinfunction "P$11_11") (pintype "bidirectional"))
    )
    (net (code "83") (name "unconnected-(MBED-P$33-Pad33)") (class "Default")
      (node (ref "MBED") (pin "33") (pinfunction "P$33_33") (pintype "bidirectional"))
    )
    (net (code "84") (name "unconnected-(MBED-P$34-Pad34)") (class "Default")
      (node (ref "MBED") (pin "34") (pinfunction "P$34_34") (pintype "bidirectional"))
    )
    (net (code "85") (name "unconnected-(MBED-P$35-Pad35)") (class "Default")
      (node (ref "MBED") (pin "35") (pinfunction "P$35_35") (pintype "bidirectional"))
    )
    (net (code "86") (name "unconnected-(MBED-P$36-Pad36)") (class "Default")
      (node (ref "MBED") (pin "36") (pinfunction "P$36_36") (pintype "bidirectional"))
    )
    (net (code "87") (name "unconnected-(RPI_HEADER-Pad1)") (class "Default")
      (node (ref "RPI_HEADER") (pin "1") (pinfunction "1_1") (pintype "passive"))
    )
    (net (code "88") (name "unconnected-(RPI_HEADER-Pad3)") (class "Default")
      (node (ref "RPI_HEADER") (pin "3") (pinfunction "3_3") (pintype "passive"))
    )
    (net (code "89") (name "unconnected-(RPI_HEADER-Pad7)") (class "Default")
      (node (ref "RPI_HEADER") (pin "7") (pinfunction "7_7") (pintype "passive"))
    )
    (net (code "90") (name "unconnected-(RPI_HEADER-Pad11)") (class "Default")
      (node (ref "RPI_HEADER") (pin "11") (pinfunction "11_11") (pintype "passive"))
    )
    (net (code "91") (name "unconnected-(RPI_HEADER-Pad12)") (class "Default")
      (node (ref "RPI_HEADER") (pin "12") (pinfunction "12_12") (pintype "passive"))
    )
    (net (code "92") (name "unconnected-(RPI_HEADER-Pad13)") (class "Default")
      (node (ref "RPI_HEADER") (pin "13") (pinfunction "13_13") (pintype "passive"))
    )
    (net (code "93") (name "unconnected-(RPI_HEADER-Pad15)") (class "Default")
      (node (ref "RPI_HEADER") (pin "15") (pinfunction "15_15") (pintype "passive"))
    )
    (net (code "94") (name "unconnected-(RPI_HEADER-Pad16)") (class "Default")
      (node (ref "RPI_HEADER") (pin "16") (pinfunction "16_16") (pintype "passive"))
    )
    (net (code "95") (name "unconnected-(RPI_HEADER-Pad17)") (class "Default")
      (node (ref "RPI_HEADER") (pin "17") (pinfunction "17_17") (pintype "passive"))
    )
    (net (code "96") (name "unconnected-(RPI_HEADER-Pad18)") (class "Default")
      (node (ref "RPI_HEADER") (pin "18") (pinfunction "18_18") (pintype "passive"))
    )
    (net (code "97") (name "unconnected-(RPI_HEADER-Pad22)") (class "Default")
      (node (ref "RPI_HEADER") (pin "22") (pinfunction "22_22") (pintype "passive"))
    )
    (net (code "98") (name "unconnected-(RPI_HEADER-Pad26)") (class "Default")
      (node (ref "RPI_HEADER") (pin "26") (pinfunction "26_26") (pintype "passive"))
    )
    (net (code "99") (name "unconnected-(RPI_HEADER-Pad27)") (class "Default")
      (node (ref "RPI_HEADER") (pin "27") (pinfunction "27_27") (pintype "passive"))
    )
    (net (code "100") (name "unconnected-(RPI_HEADER-Pad28)") (class "Default")
      (node (ref "RPI_HEADER") (pin "28") (pinfunction "28_28") (pintype "passive"))
    )
    (net (code "101") (name "unconnected-(RPI_HEADER-Pad31)") (class "Default")
      (node (ref "RPI_HEADER") (pin "31") (pinfunction "31_31") (pintype "passive"))
    )
    (net (code "102") (name "unconnected-(RPI_HEADER-Pad32)") (class "Default")
      (node (ref "RPI_HEADER") (pin "32") (pinfunction "32_32") (pintype "passive"))
    )
    (net (code "103") (name "unconnected-(RPI_HEADER-Pad33)") (class "Default")
      (node (ref "RPI_HEADER") (pin "33") (pinfunction "33_33") (pintype "passive"))
    )
    (net (code "104") (name "unconnected-(RPI_HEADER-Pad35)") (class "Default")
      (node (ref "RPI_HEADER") (pin "35") (pinfunction "35_35") (pintype "passive"))
    )
    (net (code "105") (name "unconnected-(RPI_HEADER-Pad36)") (class "Default")
      (node (ref "RPI_HEADER") (pin "36") (pinfunction "36_36") (pintype "passive"))
    )
    (net (code "106") (name "unconnected-(RPI_HEADER-Pad37)") (class "Default")
      (node (ref "RPI_HEADER") (pin "37") (pinfunction "37_37") (pintype "passive"))
    )
    (net (code "107") (name "unconnected-(RPI_HEADER-Pad38)") (class "Default")
      (node (ref "RPI_HEADER") (pin "38") (pinfunction "38_38") (pintype "passive"))
    )
    (net (code "108") (name "unconnected-(RPI_HEADER-Pad40)") (class "Default")
      (node (ref "RPI_HEADER") (pin "40") (pinfunction "40_40") (pintype "passive"))
    )
    (net (code "109") (name "unconnected-(U$4-Pad1)") (class "Default")
      (node (ref "U$4") (pin "1") (pinfunction "1_1") (pintype "passive"))
    )
    (net (code "110") (name "unconnected-(USB-Pad3)") (class "Default")
      (node (ref "USB") (pin "3") (pinfunction "3_3") (pintype "bidirectional"))
    )
    (net (code "111") (name "unconnected-(USB-Pad6)") (class "Default")
      (node (ref "USB") (pin "6") (pinfunction "6_6") (pintype "bidirectional"))
    )
  )
)
